# Carriage_Board_V2.net
KiCad netlist of a schematic drawn in EAGLE
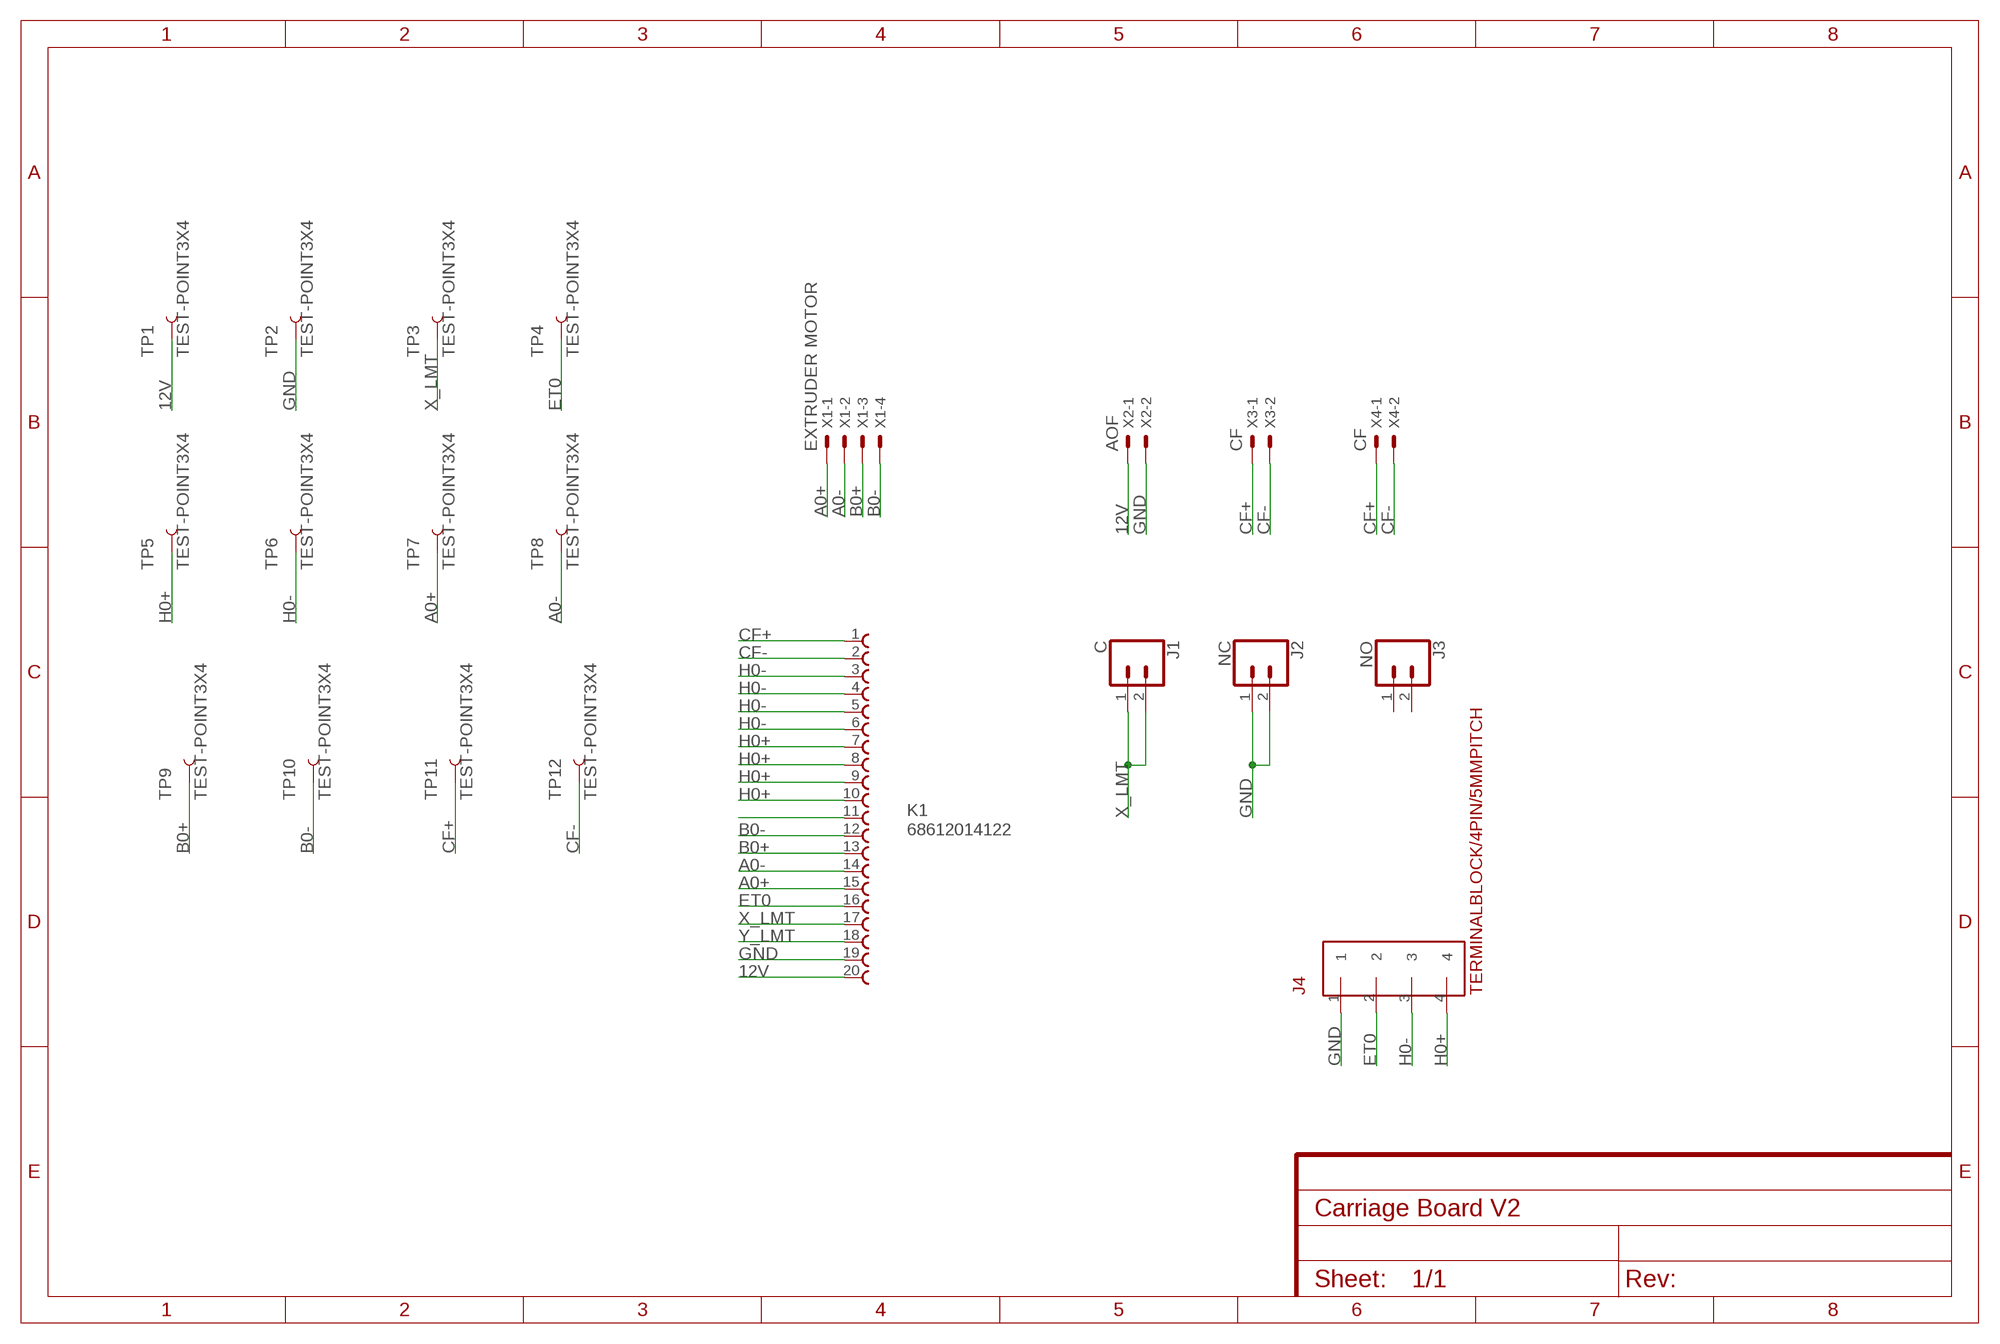
[diagram p0: schematic, sheet 1]

(export (version "E")
  (design (tool "Eeschema 10.0.6"))
  (components
    (comp (ref "J1")
      (value "C")
      (footprint "eagle-import:1X02")
      (libsource (lib "eagle-import") (part "CONN_02"))
    )
    (comp (ref "J2")
      (value "NC")
      (footprint "eagle-import:1X02")
      (libsource (lib "eagle-import") (part "CONN_02"))
    )
    (comp (ref "J3")
      (value "NO")
      (footprint "eagle-import:1X02")
      (libsource (lib "eagle-import") (part "CONN_02"))
    )
    (comp (ref "J4")
      (value "TERMINALBLOCK/4PIN/5MMPITCH")
      (footprint "eagle-import:TERMINALBLOCK_TOYO_4PIN_5MMPITCH")
      (libsource (lib "eagle-import") (part "TERMINALBLOCK/4PIN/5MMPITCH"))
    )
    (comp (ref "K1")
      (value "68612014122")
      (footprint "eagle-import:68612014122")
      (libsource (lib "eagle-import") (part "68612014122"))
    )
    (comp (ref "TP1")
      (value "TEST-POINT3X4")
      (footprint "eagle-import:PAD.03X.04")
      (libsource (lib "eagle-import") (part "TEST-POINT3X4"))
    )
    (comp (ref "TP2")
      (value "TEST-POINT3X4")
      (footprint "eagle-import:PAD.03X.04")
      (libsource (lib "eagle-import") (part "TEST-POINT3X4"))
    )
    (comp (ref "TP3")
      (value "TEST-POINT3X4")
      (footprint "eagle-import:PAD.03X.04")
      (libsource (lib "eagle-import") (part "TEST-POINT3X4"))
    )
    (comp (ref "TP4")
      (value "TEST-POINT3X4")
      (footprint "eagle-import:PAD.03X.04")
      (libsource (lib "eagle-import") (part "TEST-POINT3X4"))
    )
    (comp (ref "TP5")
      (value "TEST-POINT3X4")
      (footprint "eagle-import:PAD.03X.04")
      (libsource (lib "eagle-import") (part "TEST-POINT3X4"))
    )
    (comp (ref "TP6")
      (value "TEST-POINT3X4")
      (footprint "eagle-import:PAD.03X.04")
      (libsource (lib "eagle-import") (part "TEST-POINT3X4"))
    )
    (comp (ref "TP7")
      (value "TEST-POINT3X4")
      (footprint "eagle-import:PAD.03X.04")
      (libsource (lib "eagle-import") (part "TEST-POINT3X4"))
    )
    (comp (ref "TP8")
      (value "TEST-POINT3X4")
      (footprint "eagle-import:PAD.03X.04")
      (libsource (lib "eagle-import") (part "TEST-POINT3X4"))
    )
    (comp (ref "TP9")
      (value "TEST-POINT3X4")
      (footprint "eagle-import:PAD.03X.04")
      (libsource (lib "eagle-import") (part "TEST-POINT3X4"))
    )
    (comp (ref "TP10")
      (value "TEST-POINT3X4")
      (footprint "eagle-import:PAD.03X.04")
      (libsource (lib "eagle-import") (part "TEST-POINT3X4"))
    )
    (comp (ref "TP11")
      (value "TEST-POINT3X4")
      (footprint "eagle-import:PAD.03X.04")
      (libsource (lib "eagle-import") (part "TEST-POINT3X4"))
    )
    (comp (ref "TP12")
      (value "TEST-POINT3X4")
      (footprint "eagle-import:PAD.03X.04")
      (libsource (lib "eagle-import") (part "TEST-POINT3X4"))
    )
    (comp (ref "X1")
      (value "EXTRUDER MOTOR")
      (footprint "eagle-import:JST-XH-04-PACKAGE-LONG-PAD")
      (libsource (lib "eagle-import") (part "JST-XH-04-PIN-LONG-PAD"))
    )
    (comp (ref "X2")
      (value "AOF")
      (footprint "eagle-import:JST-XH-02-PACKAGE-LONG-PAD")
      (libsource (lib "eagle-import") (part "JST-XH-02-PIN-LONG-PAD"))
    )
    (comp (ref "X3")
      (value "CF")
      (footprint "eagle-import:JST-XH-02-PACKAGE-LONG-PAD")
      (libsource (lib "eagle-import") (part "JST-XH-02-PIN-LONG-PAD"))
    )
    (comp (ref "X4")
      (value "CF")
      (footprint "eagle-import:JST-XH-02-PACKAGE-LONG-PAD")
      (libsource (lib "eagle-import") (part "JST-XH-02-PIN-LONG-PAD"))
    )
  )
  (nets
    (net (code "1") (name "/12V") (class "Default")
      (node (ref "K1") (pin "20") (pinfunction "20_20") (pintype "passive"))
      (node (ref "TP1") (pin "P$1") (pinfunction "1_P$1") (pintype "bidirectional"))
      (node (ref "X2") (pin "1") (pinfunction "S_1") (pintype "passive"))
    )
    (net (code "2") (name "/A0+") (class "Default")
      (node (ref "K1") (pin "15") (pinfunction "15_15") (pintype "passive"))
      (node (ref "TP7") (pin "P$1") (pinfunction "1_P$1") (pintype "bidirectional"))
      (node (ref "X1") (pin "1") (pinfunction "S_1") (pintype "passive"))
    )
    (net (code "3") (name "/A0-") (class "Default")
      (node (ref "K1") (pin "14") (pinfunction "14_14") (pintype "passive"))
      (node (ref "TP8") (pin "P$1") (pinfunction "1_P$1") (pintype "bidirectional"))
      (node (ref "X1") (pin "2") (pinfunction "S_2") (pintype "passive"))
    )
    (net (code "4") (name "/B0+") (class "Default")
      (node (ref "K1") (pin "13") (pinfunction "13_13") (pintype "passive"))
      (node (ref "TP9") (pin "P$1") (pinfunction "1_P$1") (pintype "bidirectional"))
      (node (ref "X1") (pin "3") (pinfunction "S_3") (pintype "passive"))
    )
    (net (code "5") (name "/B0-") (class "Default")
      (node (ref "K1") (pin "12") (pinfunction "12_12") (pintype "passive"))
      (node (ref "TP10") (pin "P$1") (pinfunction "1_P$1") (pintype "bidirectional"))
      (node (ref "X1") (pin "4") (pinfunction "S_4") (pintype "passive"))
    )
    (net (code "6") (name "/CF+") (class "Default")
      (node (ref "K1") (pin "1") (pinfunction "1_1") (pintype "passive"))
      (node (ref "TP11") (pin "P$1") (pinfunction "1_P$1") (pintype "bidirectional"))
      (node (ref "X3") (pin "1") (pinfunction "S_1") (pintype "passive"))
      (node (ref "X4") (pin "1") (pinfunction "S_1") (pintype "passive"))
    )
    (net (code "7") (name "/CF-") (class "Default")
      (node (ref "K1") (pin "2") (pinfunction "2_2") (pintype "passive"))
      (node (ref "TP12") (pin "P$1") (pinfunction "1_P$1") (pintype "bidirectional"))
      (node (ref "X3") (pin "2") (pinfunction "S_2") (pintype "passive"))
      (node (ref "X4") (pin "2") (pinfunction "S_2") (pintype "passive"))
    )
    (net (code "8") (name "/ET0") (class "Default")
      (node (ref "J4") (pin "2") (pinfunction "2_2") (pintype "bidirectional"))
      (node (ref "K1") (pin "16") (pinfunction "16_16") (pintype "passive"))
      (node (ref "TP4") (pin "P$1") (pinfunction "1_P$1") (pintype "bidirectional"))
    )
    (net (code "9") (name "/GND") (class "Default")
      (node (ref "J2") (pin "1") (pinfunction "1_1") (pintype "passive"))
      (node (ref "J2") (pin "2") (pinfunction "2_2") (pintype "passive"))
      (node (ref "J4") (pin "1") (pinfunction "1_1") (pintype "bidirectional"))
      (node (ref "K1") (pin "19") (pinfunction "19_19") (pintype "passive"))
      (node (ref "TP2") (pin "P$1") (pinfunction "1_P$1") (pintype "bidirectional"))
      (node (ref "X2") (pin "2") (pinfunction "S_2") (pintype "passive"))
    )
    (net (code "10") (name "/H0+") (class "Default")
      (node (ref "J4") (pin "4") (pinfunction "4_4") (pintype "bidirectional"))
      (node (ref "K1") (pin "10") (pinfunction "10_10") (pintype "passive"))
      (node (ref "K1") (pin "7") (pinfunction "7_7") (pintype "passive"))
      (node (ref "K1") (pin "8") (pinfunction "8_8") (pintype "passive"))
      (node (ref "K1") (pin "9") (pinfunction "9_9") (pintype "passive"))
      (node (ref "TP5") (pin "P$1") (pinfunction "1_P$1") (pintype "bidirectional"))
    )
    (net (code "11") (name "/H0-") (class "Default")
      (node (ref "J4") (pin "3") (pinfunction "3_3") (pintype "bidirectional"))
      (node (ref "K1") (pin "3") (pinfunction "3_3") (pintype "passive"))
      (node (ref "K1") (pin "4") (pinfunction "4_4") (pintype "passive"))
      (node (ref "K1") (pin "5") (pinfunction "5_5") (pintype "passive"))
      (node (ref "K1") (pin "6") (pinfunction "6_6") (pintype "passive"))
      (node (ref "TP6") (pin "P$1") (pinfunction "1_P$1") (pintype "bidirectional"))
    )
    (net (code "12") (name "/X_LMT") (class "Default")
      (node (ref "J1") (pin "1") (pinfunction "1_1") (pintype "passive"))
      (node (ref "J1") (pin "2") (pinfunction "2_2") (pintype "passive"))
      (node (ref "K1") (pin "17") (pinfunction "17_17") (pintype "passive"))
      (node (ref "TP3") (pin "P$1") (pinfunction "1_P$1") (pintype "bidirectional"))
    )
    (net (code "13") (name "/Y_LMT") (class "Default")
      (node (ref "K1") (pin "18") (pinfunction "18_18") (pintype "passive"))
    )
    (net (code "14") (name "unconnected-(J3-Pad1)") (class "Default")
      (node (ref "J3") (pin "1") (pinfunction "1_1") (pintype "passive"))
    )
    (net (code "15") (name "unconnected-(J3-Pad2)") (class "Default")
      (node (ref "J3") (pin "2") (pinfunction "2_2") (pintype "passive"))
    )
    (net (code "16") (name "unconnected-(K1-Pad11)") (class "Default")
      (node (ref "K1") (pin "11") (pinfunction "11_11") (pintype "passive"))
    )
  )
)
